# USB_Connector.net
KiCad netlist of a schematic drawn in Altium Designer
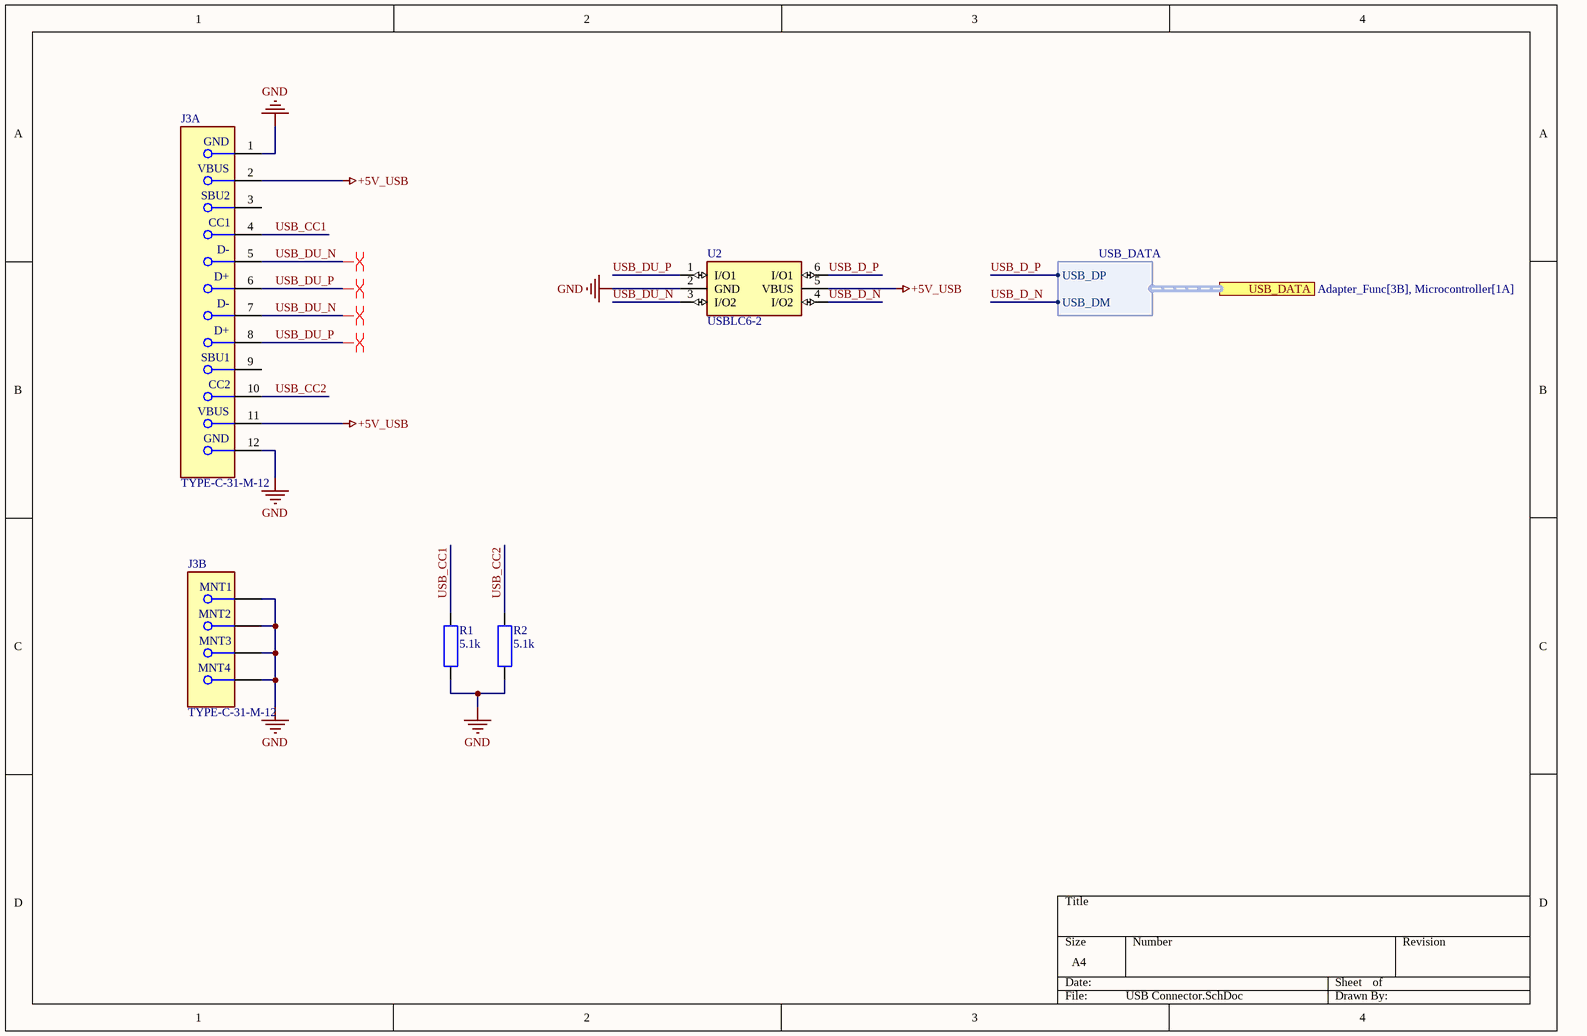
[diagram p0: USB Connector.SchDoc]

(export (version "E")
  (design (tool "Eeschema 10.0.6"))
  (components
    (comp (ref "J3")
      (value "TYPE-C-31-M-12")
      (footprint "TYPE-C-31-M-12")
      (description "5A 1 16 Female Type-C SMD USB Connectors ROHS")
      (libsource (lib "Max_lib") (part "USB-C Receptable Top Mount TYPE-C-31-M-12"))
    )
    (comp (ref "R1")
      (value "5.1k")
      (footprint "0603 SMD Res")
      (description "Resistor 5.1k 0603 1%")
      (fields (field (name "PART NUMBER") "RC0603FR-075K1L"))
      (libsource (lib "Max_lib") (part "Resistor 5.1k 0603 1%"))
    )
    (comp (ref "R2")
      (value "5.1k")
      (footprint "0603 SMD Res")
      (description "Resistor 5.1k 0603 1%")
      (fields (field (name "PART NUMBER") "RC0603FR-075K1L"))
      (libsource (lib "Max_lib") (part "Resistor 5.1k 0603 1%"))
    )
    (comp (ref "U2")
      (value "USBLC6-2")
      (footprint "SOT23-6L")
      (fields (field (name "PART NUMBER") "USBLC6-2SC6"))
      (libsource (lib "Max_lib") (part "USB ESD Protection IC USBLC6-2"))
    )
  )
  (nets
    (net (code "2") (name "+5V_USB") (class "Default")
      (node (ref "J3") (pin "11") (pinfunction "11_11") (pintype "passive"))
      (node (ref "J3") (pin "2") (pinfunction "2_2") (pintype "passive"))
      (node (ref "U2") (pin "5") (pinfunction "VBUS_5") (pintype "power_in"))
    )
    (net (code "3") (name "/USB_CC1") (class "Default")
      (node (ref "J3") (pin "4") (pinfunction "4_4") (pintype "passive"))
      (node (ref "R1") (pin "2") (pinfunction "2_2") (pintype "passive"))
    )
    (net (code "4") (name "/USB_CC2") (class "Default")
      (node (ref "J3") (pin "10") (pinfunction "10_10") (pintype "passive"))
      (node (ref "R2") (pin "2") (pinfunction "2_2") (pintype "passive"))
    )
    (net (code "5") (name "/USB_DU_N") (class "Default")
      (node (ref "J3") (pin "5") (pinfunction "5_5") (pintype "passive"))
      (node (ref "J3") (pin "7") (pinfunction "7_7") (pintype "passive"))
      (node (ref "U2") (pin "3") (pinfunction "I/O2_3") (pintype "bidirectional"))
    )
    (net (code "6") (name "/USB_DU_P") (class "Default")
      (node (ref "J3") (pin "6") (pinfunction "6_6") (pintype "passive"))
      (node (ref "J3") (pin "8") (pinfunction "8_8") (pintype "passive"))
      (node (ref "U2") (pin "1") (pinfunction "I/O1_1") (pintype "bidirectional"))
    )
    (net (code "7") (name "/USB_D_N") (class "Default")
      (node (ref "U2") (pin "4") (pinfunction "I/O2_4") (pintype "bidirectional"))
    )
    (net (code "8") (name "/USB_D_P") (class "Default")
      (node (ref "U2") (pin "6") (pinfunction "I/O1_6") (pintype "bidirectional"))
    )
    (net (code "10") (name "GND") (class "Default")
      (node (ref "J3") (pin "1") (pinfunction "1_1") (pintype "passive"))
      (node (ref "J3") (pin "12") (pinfunction "12_12") (pintype "passive"))
      (node (ref "J3") (pin "13") (pintype "passive"))
      (node (ref "J3") (pin "14") (pintype "passive"))
      (node (ref "J3") (pin "15") (pintype "passive"))
      (node (ref "J3") (pin "16") (pintype "passive"))
      (node (ref "R1") (pin "1") (pinfunction "1_1") (pintype "passive"))
      (node (ref "R2") (pin "1") (pinfunction "1_1") (pintype "passive"))
      (node (ref "U2") (pin "2") (pinfunction "GND_2") (pintype "power_in"))
    )
    (net (code "11") (name "unconnected-(J3-Pad3)") (class "Default")
      (node (ref "J3") (pin "3") (pinfunction "3_3") (pintype "passive"))
    )
    (net (code "12") (name "unconnected-(J3-Pad9)") (class "Default")
      (node (ref "J3") (pin "9") (pinfunction "9_9") (pintype "passive"))
    )
  )
)
